# JTAG_Trace.net
KiCad netlist of a schematic drawn in Altium Designer
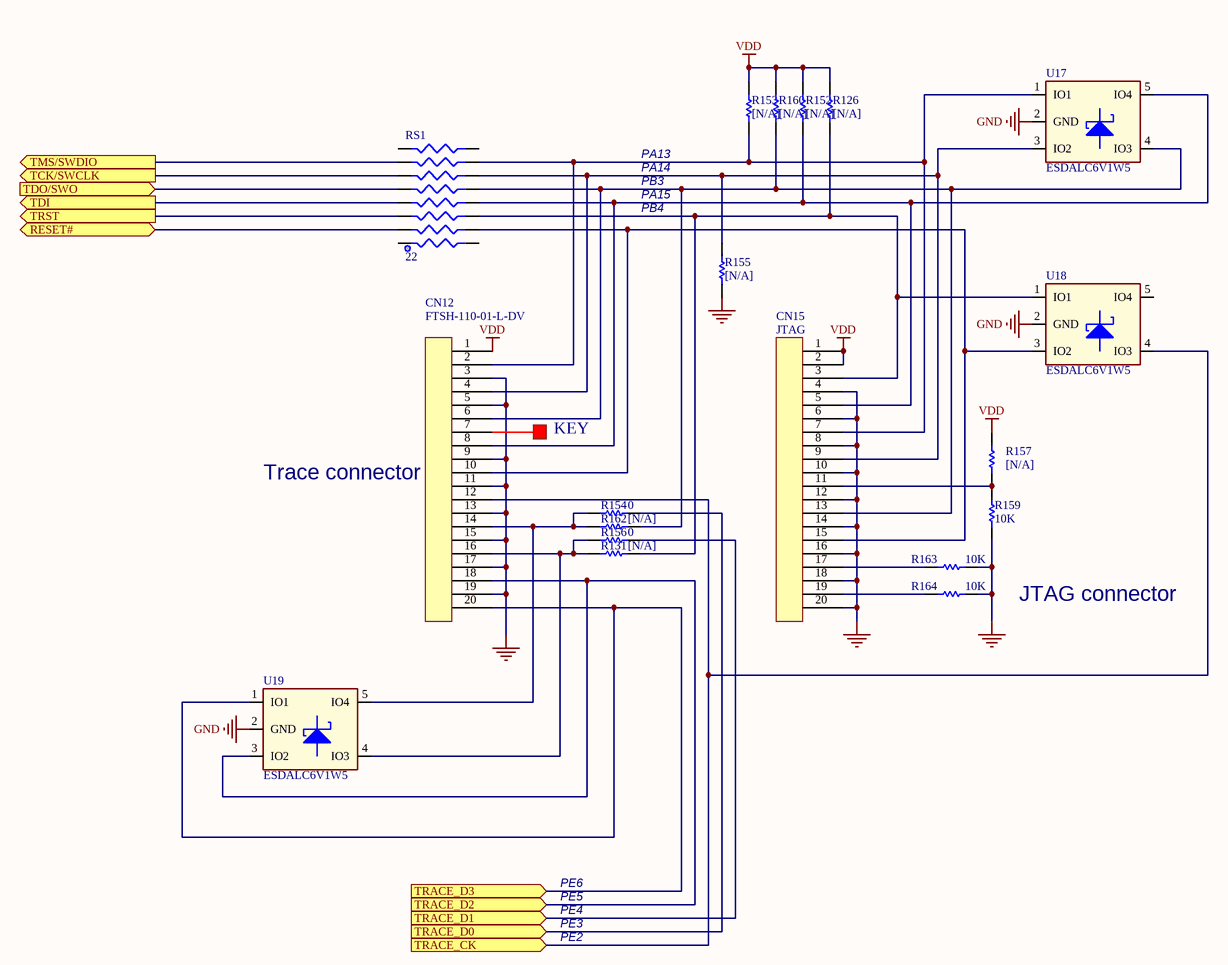
[diagram p0: JTAG&Trace.SchDoc]

(export (version "E")
  (design (tool "Eeschema 10.0.6"))
  (components
    (comp (ref "CN12")
      (value "FTSH-110-01-L-DV")
      (footprint "FTSH-110-01-L-DV")
      (libsource (lib "*") (part "20PIN1"))
    )
    (comp (ref "CN15") (value "JTAG") (footprint "IDC20S") (libsource (lib "*") (part "20PIN1")))
    (comp (ref "R126")
      (value "[N/A]")
      (footprint "0603R")
      (description "Resistor")
      (fields (field (name "PUBLISHER") "Altium Limited"))
      (libsource (lib "Miscellaneous Devices") (part "Res1"))
    )
    (comp (ref "R131")
      (value "[N/A]")
      (footprint "0603R")
      (description "Resistor")
      (fields (field (name "PUBLISHER") "Altium Limited"))
      (libsource (lib "Miscellaneous Devices") (part "Res1"))
    )
    (comp (ref "R152")
      (value "[N/A]")
      (footprint "0603R")
      (description "Resistor")
      (fields (field (name "PUBLISHER") "Altium Limited"))
      (libsource (lib "Miscellaneous Devices") (part "Res1"))
    )
    (comp (ref "R153")
      (value "[N/A]")
      (footprint "0603R")
      (description "Resistor")
      (fields (field (name "PUBLISHER") "Altium Limited"))
      (libsource (lib "Miscellaneous Devices") (part "Res1"))
    )
    (comp (ref "R154")
      (value "0")
      (footprint "0603R")
      (description "Resistor")
      (fields (field (name "PUBLISHER") "Altium Limited"))
      (libsource (lib "Miscellaneous Devices") (part "Res1"))
    )
    (comp (ref "R155")
      (value "[N/A]")
      (footprint "0603R")
      (description "Resistor")
      (fields (field (name "PUBLISHER") "Altium Limited"))
      (libsource (lib "Miscellaneous Devices") (part "Res1"))
    )
    (comp (ref "R156")
      (value "0")
      (footprint "0603R")
      (description "Resistor")
      (fields (field (name "PUBLISHER") "Altium Limited"))
      (libsource (lib "Miscellaneous Devices") (part "Res1"))
    )
    (comp (ref "R157")
      (value "[N/A]")
      (footprint "0603R")
      (description "Resistor")
      (fields (field (name "PUBLISHER") "Altium Limited"))
      (libsource (lib "Miscellaneous Devices") (part "Res1"))
    )
    (comp (ref "R159")
      (value "10K")
      (footprint "0402R")
      (description "Resistor")
      (fields (field (name "PUBLISHER") "Altium Limited"))
      (libsource (lib "Miscellaneous Devices") (part "Res1"))
    )
    (comp (ref "R160")
      (value "[N/A]")
      (footprint "0603R")
      (description "Resistor")
      (fields (field (name "PUBLISHER") "Altium Limited"))
      (libsource (lib "Miscellaneous Devices") (part "Res1"))
    )
    (comp (ref "R162")
      (value "[N/A]")
      (footprint "0603R")
      (description "Resistor")
      (fields (field (name "PUBLISHER") "Altium Limited"))
      (libsource (lib "Miscellaneous Devices") (part "Res1"))
    )
    (comp (ref "R163")
      (value "10K")
      (footprint "0402R")
      (description "Resistor")
      (fields (field (name "PUBLISHER") "Altium Limited"))
      (libsource (lib "Miscellaneous Devices") (part "Res1"))
    )
    (comp (ref "R164")
      (value "10K")
      (footprint "0402R")
      (description "Resistor")
      (fields (field (name "PUBLISHER") "Altium Limited"))
      (libsource (lib "Miscellaneous Devices") (part "Res1"))
    )
    (comp (ref "RS1") (value "22") (footprint "RP0402X8_REV") (libsource (lib "*") (part "RES8B")))
    (comp (ref "U17")
      (value "ESDALC6V1W5")
      (footprint "SOT-353")
      (description "Dual Transil array for ESD protection")
      (libsource (lib "orcaeval_3") (part "ESDALC6V1W5"))
    )
    (comp (ref "U18")
      (value "ESDALC6V1W5")
      (footprint "SOT-353")
      (description "Dual Transil array for ESD protection")
      (libsource (lib "orcaeval_3") (part "ESDALC6V1W5"))
    )
    (comp (ref "U19")
      (value "ESDALC6V1W5")
      (footprint "SOT-353")
      (description "Dual Transil array for ESD protection")
      (libsource (lib "orcaeval_3") (part "ESDALC6V1W5"))
    )
  )
  (nets
    (net (code "1") (name "/RESET#") (class "Default") (node (ref "RS1") (pin "3") (pintype "passive")))
    (net (code "2") (name "/TCK{slash}SWCLK") (class "Default")
      (node (ref "RS1") (pin "11") (pintype "passive"))
    )
    (net (code "3") (name "/TDI") (class "Default") (node (ref "RS1") (pin "7") (pintype "passive")))
    (net (code "4") (name "/TDO{slash}SWO") (class "Default")
      (node (ref "RS1") (pin "9") (pintype "passive"))
    )
    (net (code "5") (name "/TMS{slash}SWDIO") (class "Default")
      (node (ref "RS1") (pin "13") (pintype "passive"))
    )
    (net (code "6") (name "/TRACE_CK") (class "Default")
      (node (ref "CN12") (pin "12") (pintype "passive"))
      (node (ref "U18") (pin "4") (pinfunction "IO3_4") (pintype "passive"))
    )
    (net (code "7") (name "/TRACE_D0") (class "Default")
      (node (ref "R154") (pin "2") (pinfunction "2_2") (pintype "passive"))
    )
    (net (code "8") (name "/TRACE_D1") (class "Default")
      (node (ref "R156") (pin "2") (pinfunction "2_2") (pintype "passive"))
    )
    (net (code "9") (name "/TRACE_D2") (class "Default")
      (node (ref "CN12") (pin "18") (pintype "passive"))
      (node (ref "U19") (pin "3") (pinfunction "IO2_3") (pintype "passive"))
    )
    (net (code "10") (name "/TRACE_D3") (class "Default")
      (node (ref "CN12") (pin "20") (pintype "passive"))
      (node (ref "U19") (pin "1") (pinfunction "IO1_1") (pintype "passive"))
    )
    (net (code "11") (name "/TRST") (class "Default") (node (ref "RS1") (pin "5") (pintype "passive")))
    (net (code "12") (name "GND") (class "Default")
      (node (ref "CN12") (pin "11") (pintype "passive"))
      (node (ref "CN12") (pin "13") (pintype "passive"))
      (node (ref "CN12") (pin "15") (pintype "passive"))
      (node (ref "CN12") (pin "17") (pintype "passive"))
      (node (ref "CN12") (pin "19") (pintype "passive"))
      (node (ref "CN12") (pin "3") (pintype "passive"))
      (node (ref "CN12") (pin "5") (pintype "passive"))
      (node (ref "CN12") (pin "9") (pintype "passive"))
      (node (ref "CN15") (pin "10") (pintype "passive"))
      (node (ref "CN15") (pin "12") (pintype "passive"))
      (node (ref "CN15") (pin "14") (pintype "passive"))
      (node (ref "CN15") (pin "16") (pintype "passive"))
      (node (ref "CN15") (pin "18") (pintype "passive"))
      (node (ref "CN15") (pin "20") (pintype "passive"))
      (node (ref "CN15") (pin "4") (pintype "passive"))
      (node (ref "CN15") (pin "6") (pintype "passive"))
      (node (ref "CN15") (pin "8") (pintype "passive"))
      (node (ref "R155") (pin "1") (pinfunction "1_1") (pintype "passive"))
      (node (ref "R159") (pin "1") (pinfunction "1_1") (pintype "passive"))
      (node (ref "R163") (pin "1") (pinfunction "1_1") (pintype "passive"))
      (node (ref "R164") (pin "1") (pinfunction "1_1") (pintype "passive"))
      (node (ref "U17") (pin "2") (pinfunction "GND_2") (pintype "passive"))
      (node (ref "U18") (pin "2") (pinfunction "GND_2") (pintype "passive"))
      (node (ref "U19") (pin "2") (pinfunction "GND_2") (pintype "passive"))
    )
    (net (code "13") (name "Net-(CN15-Pad11)") (class "Default")
      (node (ref "CN15") (pin "11") (pintype "passive"))
      (node (ref "R157") (pin "1") (pinfunction "1_1") (pintype "passive"))
      (node (ref "R159") (pin "2") (pinfunction "2_2") (pintype "passive"))
    )
    (net (code "14") (name "Net-(CN15-Pad17)") (class "Default")
      (node (ref "CN15") (pin "17") (pintype "passive"))
      (node (ref "R163") (pin "2") (pinfunction "2_2") (pintype "passive"))
    )
    (net (code "15") (name "Net-(CN15-Pad19)") (class "Default")
      (node (ref "CN15") (pin "19") (pintype "passive"))
      (node (ref "R164") (pin "2") (pinfunction "2_2") (pintype "passive"))
    )
    (net (code "16") (name "Net-(U17-IO1)") (class "Default")
      (node (ref "CN12") (pin "2") (pintype "passive"))
      (node (ref "CN15") (pin "7") (pintype "passive"))
      (node (ref "R153") (pin "1") (pinfunction "1_1") (pintype "passive"))
      (node (ref "RS1") (pin "14") (pintype "passive"))
      (node (ref "U17") (pin "1") (pinfunction "IO1_1") (pintype "passive"))
    )
    (net (code "17") (name "Net-(U17-IO2)") (class "Default")
      (node (ref "CN12") (pin "4") (pintype "passive"))
      (node (ref "CN15") (pin "9") (pintype "passive"))
      (node (ref "R155") (pin "2") (pinfunction "2_2") (pintype "passive"))
      (node (ref "RS1") (pin "12") (pintype "passive"))
      (node (ref "U17") (pin "3") (pinfunction "IO2_3") (pintype "passive"))
    )
    (net (code "18") (name "Net-(U17-IO3)") (class "Default")
      (node (ref "CN12") (pin "6") (pintype "passive"))
      (node (ref "CN15") (pin "13") (pintype "passive"))
      (node (ref "R160") (pin "1") (pinfunction "1_1") (pintype "passive"))
      (node (ref "R162") (pin "2") (pinfunction "2_2") (pintype "passive"))
      (node (ref "RS1") (pin "10") (pintype "passive"))
      (node (ref "U17") (pin "4") (pinfunction "IO3_4") (pintype "passive"))
    )
    (net (code "19") (name "Net-(U17-IO4)") (class "Default")
      (node (ref "CN12") (pin "8") (pintype "passive"))
      (node (ref "CN15") (pin "5") (pintype "passive"))
      (node (ref "R152") (pin "1") (pinfunction "1_1") (pintype "passive"))
      (node (ref "RS1") (pin "8") (pintype "passive"))
      (node (ref "U17") (pin "5") (pinfunction "IO4_5") (pintype "passive"))
    )
    (net (code "20") (name "Net-(U18-IO1)") (class "Default")
      (node (ref "CN15") (pin "3") (pintype "passive"))
      (node (ref "R126") (pin "1") (pinfunction "1_1") (pintype "passive"))
      (node (ref "R131") (pin "2") (pinfunction "2_2") (pintype "passive"))
      (node (ref "RS1") (pin "6") (pintype "passive"))
      (node (ref "U18") (pin "1") (pinfunction "IO1_1") (pintype "passive"))
    )
    (net (code "21") (name "Net-(U18-IO2)") (class "Default")
      (node (ref "CN12") (pin "10") (pintype "passive"))
      (node (ref "CN15") (pin "15") (pintype "passive"))
      (node (ref "RS1") (pin "4") (pintype "passive"))
      (node (ref "U18") (pin "3") (pinfunction "IO2_3") (pintype "passive"))
    )
    (net (code "22") (name "Net-(U19-IO3)") (class "Default")
      (node (ref "CN12") (pin "16") (pintype "passive"))
      (node (ref "R131") (pin "1") (pinfunction "1_1") (pintype "passive"))
      (node (ref "R156") (pin "1") (pinfunction "1_1") (pintype "passive"))
      (node (ref "U19") (pin "4") (pinfunction "IO3_4") (pintype "passive"))
    )
    (net (code "23") (name "Net-(U19-IO4)") (class "Default")
      (node (ref "CN12") (pin "14") (pintype "passive"))
      (node (ref "R154") (pin "1") (pinfunction "1_1") (pintype "passive"))
      (node (ref "R162") (pin "1") (pinfunction "1_1") (pintype "passive"))
      (node (ref "U19") (pin "5") (pinfunction "IO4_5") (pintype "passive"))
    )
    (net (code "24") (name "VDD") (class "Default")
      (node (ref "CN12") (pin "1") (pintype "passive"))
      (node (ref "CN15") (pin "1") (pintype "passive"))
      (node (ref "CN15") (pin "2") (pintype "passive"))
      (node (ref "R126") (pin "2") (pinfunction "2_2") (pintype "passive"))
      (node (ref "R152") (pin "2") (pinfunction "2_2") (pintype "passive"))
      (node (ref "R153") (pin "2") (pinfunction "2_2") (pintype "passive"))
      (node (ref "R157") (pin "2") (pinfunction "2_2") (pintype "passive"))
      (node (ref "R160") (pin "2") (pinfunction "2_2") (pintype "passive"))
    )
    (net (code "25") (name "unconnected-(CN12-Pad7)") (class "Default")
      (node (ref "CN12") (pin "7") (pintype "passive"))
    )
    (net (code "26") (name "unconnected-(RS1-Pad1)") (class "Default")
      (node (ref "RS1") (pin "1") (pintype "passive"))
    )
    (net (code "27") (name "unconnected-(RS1-Pad2)") (class "Default")
      (node (ref "RS1") (pin "2") (pintype "passive"))
    )
    (net (code "28") (name "unconnected-(RS1-Pad15)") (class "Default")
      (node (ref "RS1") (pin "15") (pintype "passive"))
    )
    (net (code "29") (name "unconnected-(RS1-Pad16)") (class "Default")
      (node (ref "RS1") (pin "16") (pintype "passive"))
    )
    (net (code "30") (name "unconnected-(U18-IO4-Pad5)") (class "Default")
      (node (ref "U18") (pin "5") (pinfunction "IO4_5") (pintype "passive"))
    )
  )
)
